# DSO_Trig.net
KiCad netlist of a schematic drawn in Altium Designer
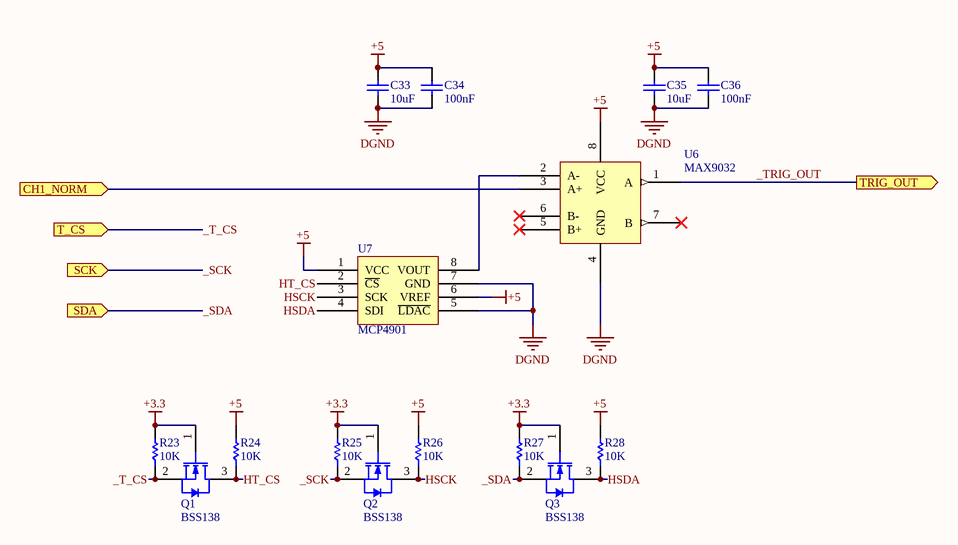
[diagram p0: DSO_Trig.SchDoc]

(export (version "E")
  (design (tool "Eeschema 10.0.6"))
  (components
    (comp (ref "C33")
      (value "10uF")
      (footprint "0805C")
      (description "Capacitor")
      (fields (field (name "REVIEWED BY") "RM - 2018/08/05"))
      (libsource (lib "DSO") (part "C"))
    )
    (comp (ref "C34")
      (value "100nF")
      (footprint "0805C")
      (description "Capacitor")
      (fields (field (name "REVIEWED BY") "RM - 2018/08/05"))
      (libsource (lib "DSO") (part "C"))
    )
    (comp (ref "C35")
      (value "10uF")
      (footprint "0805C")
      (description "Capacitor")
      (fields (field (name "REVIEWED BY") "RM - 2018/08/05"))
      (libsource (lib "DSO") (part "C"))
    )
    (comp (ref "C36")
      (value "100nF")
      (footprint "0805C")
      (description "Capacitor")
      (fields (field (name "REVIEWED BY") "RM - 2018/08/05"))
      (libsource (lib "DSO") (part "C"))
    )
    (comp (ref "Q1")
      (value "BSS138")
      (footprint "SOT23")
      (description "N-Channel MOSFET")
      (fields (field (name "PUBLISHER") "Altium Limited"))
      (libsource (lib "DSO") (part "MOSFET-N"))
    )
    (comp (ref "Q2")
      (value "BSS138")
      (footprint "SOT23")
      (description "N-Channel MOSFET")
      (fields (field (name "PUBLISHER") "Altium Limited"))
      (libsource (lib "DSO") (part "MOSFET-N"))
    )
    (comp (ref "Q3")
      (value "BSS138")
      (footprint "SOT23")
      (description "N-Channel MOSFET")
      (fields (field (name "PUBLISHER") "Altium Limited"))
      (libsource (lib "DSO") (part "MOSFET-N"))
    )
    (comp (ref "R23")
      (value "10K")
      (footprint "0805")
      (description "Resistor")
      (fields (field (name "REVIEWED BY") "RM - 2018/08/05"))
      (libsource (lib "DSO") (part "R"))
    )
    (comp (ref "R24")
      (value "10K")
      (footprint "0805")
      (description "Resistor")
      (fields (field (name "REVIEWED BY") "RM - 2018/08/05"))
      (libsource (lib "DSO") (part "R"))
    )
    (comp (ref "R25")
      (value "10K")
      (footprint "0805")
      (description "Resistor")
      (fields (field (name "REVIEWED BY") "RM - 2018/08/05"))
      (libsource (lib "DSO") (part "R"))
    )
    (comp (ref "R26")
      (value "10K")
      (footprint "0805")
      (description "Resistor")
      (fields (field (name "REVIEWED BY") "RM - 2018/08/05"))
      (libsource (lib "DSO") (part "R"))
    )
    (comp (ref "R27")
      (value "10K")
      (footprint "0805")
      (description "Resistor")
      (fields (field (name "REVIEWED BY") "RM - 2018/08/05"))
      (libsource (lib "DSO") (part "R"))
    )
    (comp (ref "R28")
      (value "10K")
      (footprint "0805")
      (description "Resistor")
      (fields (field (name "REVIEWED BY") "RM - 2018/08/05"))
      (libsource (lib "DSO") (part "R"))
    )
    (comp (ref "U6")
      (value "MAX9032")
      (footprint "SOIC-8")
      (description "Dual Comparator")
      (fields (field (name "REVIEWED BY") "RM - 2018/08/05"))
      (libsource (lib "DSO") (part "MAX9032"))
    )
    (comp (ref "U7")
      (value "MCP4901")
      (footprint "SOIC-8")
      (description "DAC 8bit SPI")
      (fields (field (name "REVIEWED BY") "RM - 2018/08/05"))
      (libsource (lib "DSO") (part "MCP4901"))
    )
  )
  (nets
    (net (code "1") (name "+3.3") (class "Default")
      (node (ref "Q1") (pin "1") (pinfunction "G_1") (pintype "passive"))
      (node (ref "Q2") (pin "1") (pinfunction "G_1") (pintype "passive"))
      (node (ref "Q3") (pin "1") (pinfunction "G_1") (pintype "passive"))
      (node (ref "R23") (pin "2") (pintype "passive"))
      (node (ref "R25") (pin "2") (pintype "passive"))
      (node (ref "R27") (pin "2") (pintype "passive"))
    )
    (net (code "2") (name "+5") (class "Default")
      (node (ref "C33") (pin "1") (pinfunction "1_1") (pintype "passive"))
      (node (ref "C34") (pin "1") (pinfunction "1_1") (pintype "passive"))
      (node (ref "C35") (pin "1") (pinfunction "1_1") (pintype "passive"))
      (node (ref "C36") (pin "1") (pinfunction "1_1") (pintype "passive"))
      (node (ref "R24") (pin "2") (pintype "passive"))
      (node (ref "R26") (pin "2") (pintype "passive"))
      (node (ref "R28") (pin "2") (pintype "passive"))
      (node (ref "U6") (pin "8") (pinfunction "VCC_8") (pintype "passive"))
      (node (ref "U7") (pin "1") (pinfunction "VCC_1") (pintype "passive"))
      (node (ref "U7") (pin "6") (pinfunction "VREF_6") (pintype "passive"))
    )
    (net (code "3") (name "/CH1_NORM") (class "Default")
      (node (ref "U6") (pin "3") (pinfunction "A+_3") (pintype "passive"))
    )
    (net (code "4") (name "/HSCK") (class "Default")
      (node (ref "Q2") (pin "3") (pinfunction "D_3") (pintype "passive"))
      (node (ref "R26") (pin "1") (pintype "passive"))
      (node (ref "U7") (pin "3") (pinfunction "SCK_3") (pintype "passive"))
    )
    (net (code "5") (name "/HSDA") (class "Default")
      (node (ref "Q3") (pin "3") (pinfunction "D_3") (pintype "passive"))
      (node (ref "R28") (pin "1") (pintype "passive"))
      (node (ref "U7") (pin "4") (pinfunction "SDI_4") (pintype "passive"))
    )
    (net (code "6") (name "/HT_CS") (class "Default")
      (node (ref "Q1") (pin "3") (pinfunction "D_3") (pintype "passive"))
      (node (ref "R24") (pin "1") (pintype "passive"))
      (node (ref "U7") (pin "2") (pinfunction "~{CS}_2") (pintype "passive"))
    )
    (net (code "7") (name "/_SCK") (class "Default")
      (node (ref "Q2") (pin "2") (pinfunction "S_2") (pintype "passive"))
      (node (ref "R25") (pin "1") (pintype "passive"))
    )
    (net (code "8") (name "/_SDA") (class "Default")
      (node (ref "Q3") (pin "2") (pinfunction "S_2") (pintype "passive"))
      (node (ref "R27") (pin "1") (pintype "passive"))
    )
    (net (code "9") (name "/_TRIG_OUT") (class "Default")
      (node (ref "U6") (pin "1") (pinfunction "A_1") (pintype "output"))
    )
    (net (code "10") (name "/_T_CS") (class "Default")
      (node (ref "Q1") (pin "2") (pinfunction "S_2") (pintype "passive"))
      (node (ref "R23") (pin "1") (pintype "passive"))
    )
    (net (code "11") (name "DGND") (class "Default")
      (node (ref "C33") (pin "2") (pinfunction "2_2") (pintype "passive"))
      (node (ref "C34") (pin "2") (pinfunction "2_2") (pintype "passive"))
      (node (ref "C35") (pin "2") (pinfunction "2_2") (pintype "passive"))
      (node (ref "C36") (pin "2") (pinfunction "2_2") (pintype "passive"))
      (node (ref "U6") (pin "4") (pinfunction "GND_4") (pintype "passive"))
      (node (ref "U7") (pin "5") (pinfunction "~{LDAC}_5") (pintype "passive"))
      (node (ref "U7") (pin "7") (pinfunction "GND_7") (pintype "passive"))
    )
    (net (code "12") (name "Net-(U6-A-)") (class "Default")
      (node (ref "U6") (pin "2") (pinfunction "A-_2") (pintype "passive"))
      (node (ref "U7") (pin "8") (pinfunction "VOUT_8") (pintype "passive"))
    )
    (net (code "13") (name "unconnected-(U6-B+-Pad5)") (class "Default")
      (node (ref "U6") (pin "5") (pinfunction "B+_5") (pintype "passive+no_connect"))
    )
    (net (code "14") (name "unconnected-(U6-B--Pad6)") (class "Default")
      (node (ref "U6") (pin "6") (pinfunction "B-_6") (pintype "passive+no_connect"))
    )
    (net (code "15") (name "unconnected-(U6-B-Pad7)") (class "Default")
      (node (ref "U6") (pin "7") (pinfunction "B_7") (pintype "output+no_connect"))
    )
  )
)
